# GPIO_Audio_DLT.net
KiCad netlist of a schematic drawn in EAGLE
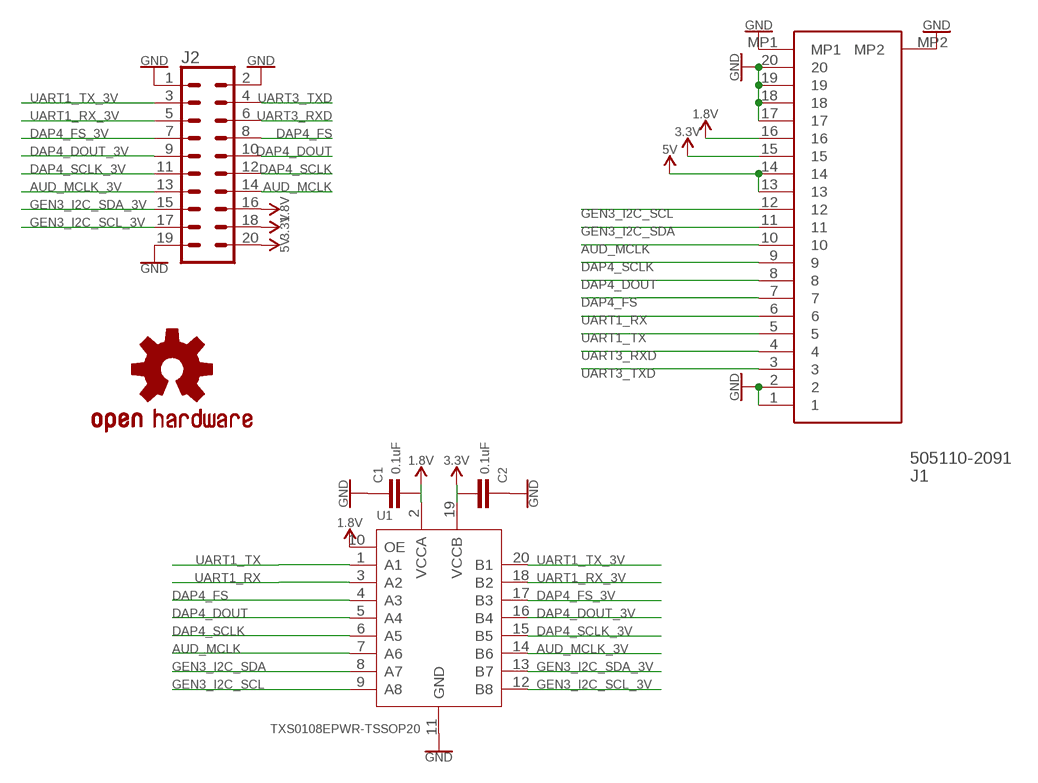
[diagram p0: schematic, sheet 1]

(export (version "E")
  (design (tool "Eeschema 10.0.6"))
  (components
    (comp (ref "C1")
      (value "0.1uF")
      (footprint "eagle-import:0603")
      (libsource (lib "eagle-import") (part "10NF-0603-50V-10%"))
    )
    (comp (ref "C2")
      (value "0.1uF")
      (footprint "eagle-import:0603")
      (libsource (lib "eagle-import") (part "10NF-0603-50V-10%"))
    )
    (comp (ref "J1")
      (value "505110-2091")
      (footprint "eagle-import:5051102091")
      (fields (field (name "MOUSER_PART_NUMBER") "538-505110-2091"))
      (libsource (lib "eagle-import") (part "505110-2091"))
    )
    (comp (ref "J2")
      (value "CONN_10X2")
      (footprint "eagle-import:2X10")
      (libsource (lib "eagle-import") (part "CONN_10X2"))
    )
    (comp (ref "LOGO1")
      (value "OSHW-LOGOS-COPPER")
      (footprint "eagle-import:OSHW-LOGO-S_COPPER")
      (libsource (lib "eagle-import") (part "OSHW-LOGOS-COPPER"))
    )
    (comp (ref "U1")
      (value "TXS0108EPWR-TSSOP20")
      (footprint "eagle-import:TSSOP20-0.65-6.5X4.4MM")
      (fields (field (name "MPN") "TXS0108EPWR"))
      (libsource (lib "eagle-import") (part "LOGIC-TXS0108EPWR(TSSOP20)"))
    )
  )
  (nets
    (net (code "1") (name "/AUD_MCLK") (class "Default")
      (node (ref "J1") (pin "10") (pinfunction "10_10") (pintype "bidirectional"))
      (node (ref "J2") (pin "14") (pinfunction "14_14") (pintype "passive"))
      (node (ref "U1") (pin "7") (pinfunction "A6_7") (pintype "bidirectional"))
    )
    (net (code "2") (name "/AUD_MCLK_3V") (class "Default")
      (node (ref "J2") (pin "13") (pinfunction "13_13") (pintype "passive"))
      (node (ref "U1") (pin "14") (pinfunction "B6_14") (pintype "bidirectional"))
    )
    (net (code "3") (name "/DAP4_DOUT") (class "Default")
      (node (ref "J1") (pin "8") (pinfunction "8_8") (pintype "bidirectional"))
      (node (ref "J2") (pin "10") (pinfunction "10_10") (pintype "passive"))
      (node (ref "U1") (pin "5") (pinfunction "A4_5") (pintype "bidirectional"))
    )
    (net (code "4") (name "/DAP4_DOUT_3V") (class "Default")
      (node (ref "J2") (pin "9") (pinfunction "9_9") (pintype "passive"))
      (node (ref "U1") (pin "16") (pinfunction "B4_16") (pintype "bidirectional"))
    )
    (net (code "5") (name "/DAP4_FS") (class "Default")
      (node (ref "J1") (pin "7") (pinfunction "7_7") (pintype "bidirectional"))
      (node (ref "J2") (pin "8") (pinfunction "8_8") (pintype "passive"))
      (node (ref "U1") (pin "4") (pinfunction "A3_4") (pintype "bidirectional"))
    )
    (net (code "6") (name "/DAP4_FS_3V") (class "Default")
      (node (ref "J2") (pin "7") (pinfunction "7_7") (pintype "passive"))
      (node (ref "U1") (pin "17") (pinfunction "B3_17") (pintype "bidirectional"))
    )
    (net (code "7") (name "/DAP4_SCLK") (class "Default")
      (node (ref "J1") (pin "9") (pinfunction "9_9") (pintype "bidirectional"))
      (node (ref "J2") (pin "12") (pinfunction "12_12") (pintype "passive"))
      (node (ref "U1") (pin "6") (pinfunction "A5_6") (pintype "bidirectional"))
    )
    (net (code "8") (name "/DAP4_SCLK_3V") (class "Default")
      (node (ref "J2") (pin "11") (pinfunction "11_11") (pintype "passive"))
      (node (ref "U1") (pin "15") (pinfunction "B5_15") (pintype "bidirectional"))
    )
    (net (code "9") (name "/GEN3_I2C_SCL") (class "Default")
      (node (ref "J1") (pin "12") (pinfunction "12_12") (pintype "bidirectional"))
      (node (ref "U1") (pin "9") (pinfunction "A8_9") (pintype "bidirectional"))
    )
    (net (code "10") (name "/GEN3_I2C_SCL_3V") (class "Default")
      (node (ref "J2") (pin "17") (pinfunction "17_17") (pintype "passive"))
      (node (ref "U1") (pin "12") (pinfunction "B8_12") (pintype "bidirectional"))
    )
    (net (code "11") (name "/GEN3_I2C_SDA") (class "Default")
      (node (ref "J1") (pin "11") (pinfunction "11_11") (pintype "bidirectional"))
      (node (ref "U1") (pin "8") (pinfunction "A7_8") (pintype "bidirectional"))
    )
    (net (code "12") (name "/GEN3_I2C_SDA_3V") (class "Default")
      (node (ref "J2") (pin "15") (pinfunction "15_15") (pintype "passive"))
      (node (ref "U1") (pin "13") (pinfunction "B7_13") (pintype "bidirectional"))
    )
    (net (code "13") (name "/UART1_RX") (class "Default")
      (node (ref "J1") (pin "6") (pinfunction "6_6") (pintype "bidirectional"))
      (node (ref "U1") (pin "3") (pinfunction "A2_3") (pintype "bidirectional"))
    )
    (net (code "14") (name "/UART1_RX_3V") (class "Default")
      (node (ref "J2") (pin "5") (pinfunction "5_5") (pintype "passive"))
      (node (ref "U1") (pin "18") (pinfunction "B2_18") (pintype "bidirectional"))
    )
    (net (code "15") (name "/UART1_TX") (class "Default")
      (node (ref "J1") (pin "5") (pinfunction "5_5") (pintype "bidirectional"))
      (node (ref "U1") (pin "1") (pinfunction "A1_1") (pintype "bidirectional"))
    )
    (net (code "16") (name "/UART1_TX_3V") (class "Default")
      (node (ref "J2") (pin "3") (pinfunction "3_3") (pintype "passive"))
      (node (ref "U1") (pin "20") (pinfunction "B1_20") (pintype "bidirectional"))
    )
    (net (code "17") (name "/UART3_RXD") (class "Default")
      (node (ref "J1") (pin "4") (pinfunction "4_4") (pintype "bidirectional"))
      (node (ref "J2") (pin "6") (pinfunction "6_6") (pintype "passive"))
    )
    (net (code "18") (name "/UART3_TXD") (class "Default")
      (node (ref "J1") (pin "3") (pinfunction "3_3") (pintype "bidirectional"))
      (node (ref "J2") (pin "4") (pinfunction "4_4") (pintype "passive"))
    )
    (net (code "19") (name "1.8V") (class "Default")
      (node (ref "C1") (pin "2") (pinfunction "2_2") (pintype "passive"))
      (node (ref "J1") (pin "16") (pinfunction "16_16") (pintype "bidirectional"))
      (node (ref "J2") (pin "16") (pinfunction "16_16") (pintype "passive"))
      (node (ref "U1") (pin "10") (pinfunction "OE_10") (pintype "bidirectional"))
      (node (ref "U1") (pin "2") (pinfunction "VCCA_2") (pintype "bidirectional"))
    )
    (net (code "20") (name "3.3V") (class "Default")
      (node (ref "C2") (pin "1") (pinfunction "1_1") (pintype "passive"))
      (node (ref "J1") (pin "15") (pinfunction "15_15") (pintype "bidirectional"))
      (node (ref "J2") (pin "18") (pinfunction "18_18") (pintype "passive"))
      (node (ref "U1") (pin "19") (pinfunction "VCCB_19") (pintype "bidirectional"))
    )
    (net (code "21") (name "5V") (class "Default")
      (node (ref "J1") (pin "13") (pinfunction "13_13") (pintype "bidirectional"))
      (node (ref "J1") (pin "14") (pinfunction "14_14") (pintype "bidirectional"))
      (node (ref "J2") (pin "20") (pinfunction "20_20") (pintype "passive"))
    )
    (net (code "22") (name "GND") (class "Default")
      (node (ref "C1") (pin "1") (pinfunction "1_1") (pintype "passive"))
      (node (ref "C2") (pin "2") (pinfunction "2_2") (pintype "passive"))
      (node (ref "J1") (pin "1") (pinfunction "1_1") (pintype "bidirectional"))
      (node (ref "J1") (pin "17") (pinfunction "17_17") (pintype "bidirectional"))
      (node (ref "J1") (pin "18") (pinfunction "18_18") (pintype "bidirectional"))
      (node (ref "J1") (pin "19") (pinfunction "19_19") (pintype "bidirectional"))
      (node (ref "J1") (pin "2") (pinfunction "2_2") (pintype "bidirectional"))
      (node (ref "J1") (pin "20") (pinfunction "20_20") (pintype "bidirectional"))
      (node (ref "J1") (pin "MP1") (pinfunction "MP1_MP1") (pintype "bidirectional"))
      (node (ref "J1") (pin "MP2") (pinfunction "MP2_MP2") (pintype "bidirectional"))
      (node (ref "J2") (pin "1") (pinfunction "1_1") (pintype "passive"))
      (node (ref "J2") (pin "19") (pinfunction "19_19") (pintype "passive"))
      (node (ref "J2") (pin "2") (pinfunction "2_2") (pintype "passive"))
      (node (ref "U1") (pin "11") (pinfunction "GND_11") (pintype "bidirectional"))
    )
  )
)
